# 90_IR_Receiver_LED.net
KiCad netlist of a schematic drawn in Altium Designer
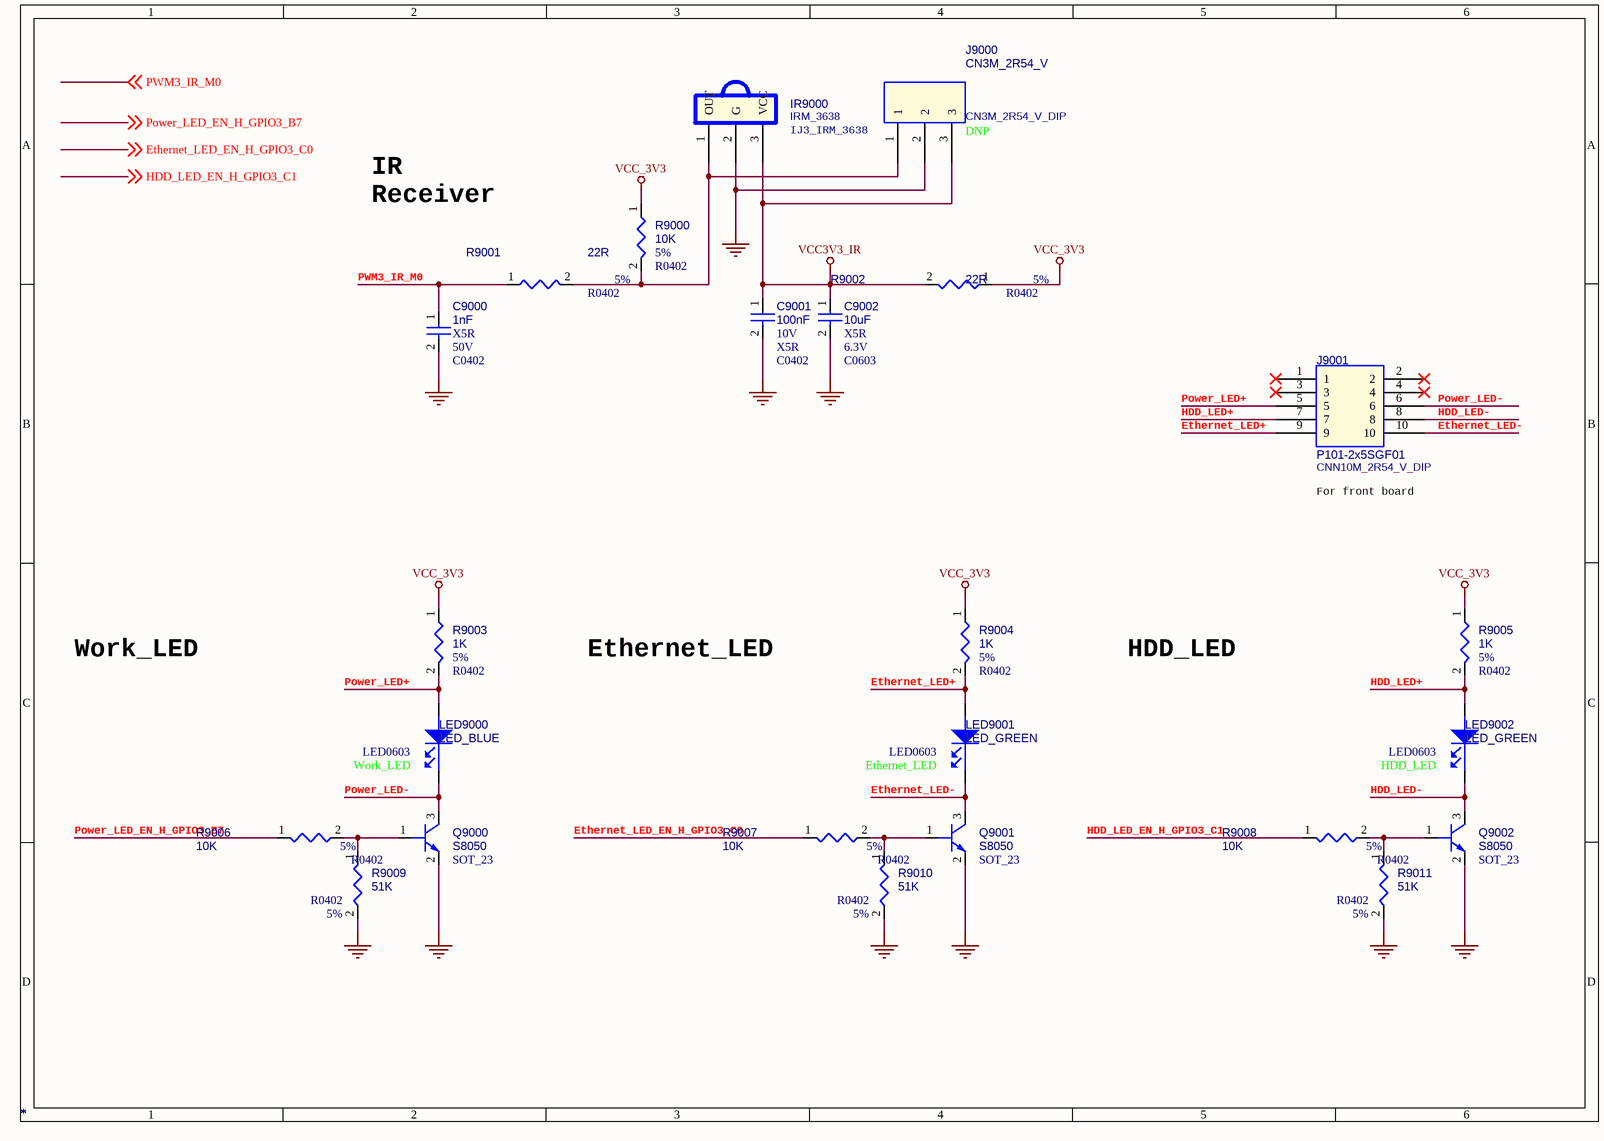
[diagram p0: 90.IR Receiver_LED.SchDoc]

(export (version "E")
  (design (tool "Eeschema 10.0.6"))
  (components
    (comp (ref "C9000")
      (value "*")
      (footprint "C0402")
      (description "cap,1.00nF,+/-10%,50V,X5R,C0402")
      (fields
        (field (name "VOLTAGE") "50V")
        (field (name "PCB FOOTPRINT") "C0402")
        (field (name "DIELECTRIC") "X5R")
        (field (name "MANUFACTURER") "TDK")
        (field (name "TOLERANCE") "10%")
        (field (name "ALTIUM_UNNAMED_1") "1nF")
        (field (name "CREATED BY") "JJJ")
      )
      (libsource (lib "*") (part "CAP NP"))
    )
    (comp (ref "C9001")
      (value "*")
      (footprint "C0402")
      (description "cap,100.00nF,+/-10%,10V,X5R,C0402")
      (fields
        (field (name "VOLTAGE") "10V")
        (field (name "PCB FOOTPRINT") "C0402")
        (field (name "DIELECTRIC") "X5R")
        (field (name "MANUFACTURER") "TDK")
        (field (name "TOLERANCE") "10%")
        (field (name "ALTIUM_UNNAMED_1") "100nF")
        (field (name "CREATED BY") "JJJ")
      )
      (libsource (lib "*") (part "CAP NP"))
    )
    (comp (ref "C9002")
      (value "*")
      (footprint "C0603")
      (description "cap,10.00uF,+/-10%,6.3V,X5R,C0603")
      (fields
        (field (name "VOLTAGE") "6.3V")
        (field (name "PCB FOOTPRINT") "C0603")
        (field (name "DIELECTRIC") "X5R")
        (field (name "MANUFACTURER") "TDK")
        (field (name "TOLERANCE") "10%")
        (field (name "ALTIUM_UNNAMED_1") "10uF")
        (field (name "CREATED BY") "JJJ")
      )
      (libsource (lib "*") (part "CAP NP"))
    )
    (comp (ref "IR9000")
      (value "*")
      (footprint "IR3DIP")
      (description "ємНвЅУКХН·")
      (fields
        (field (name "PCB FOOTPRINT") "IJ3_IRM_3638")
        (field (name "MANUFACTURER") "ТЪ№в")
        (field (name "MANUFACTURER PART NUMBER") "IRM_3638")
        (field (name "ALTIUM_UNNAMED_1") "IRM_3638")
        (field (name "CREATED BY") "JJJ")
      )
      (libsource (lib "*") (part "IRM_0"))
    )
    (comp (ref "J9000")
      (value "*")
      (footprint "DIP3_1X3_2R54")
      (description "µҐЕЕ3PINЈЁјдѕа2.54mmЈ©І»ґш·А»¤ЗЅµДІеХл")
      (fields
        (field (name "PCB FOOTPRINT") "CN3M_2R54_V_DIP")
        (field (name "OPTION") "DNP")
        (field (name "MANUFACTURER") "НъїЖґп")
        (field (name "MANUFACTURER PART NUMBER") "CON3M_1X3_2R54_V")
        (field (name "ALTIUM_UNNAMED_1") "CN3M_2R54_V")
        (field (name "CREATED BY") "JJJ")
      )
      (libsource (lib "*") (part "CON3_1X3"))
    )
    (comp (ref "J9001")
      (value "*")
      (footprint "JTAG_2X10_2R54")
      (description "Л«ЕЕ10PINЈЁјдѕа2.54mmЈ©І»ґш·А»¤ЗЅµДІеХл,БўКЅЈ¬№«Чщ")
      (fields
        (field (name "PCB FOOTPRINT") "CNN10M_2R54_V_DIP")
        (field (name "MANUFACTURER") "СwХэµзЧУ")
        (field (name "MANUFACTURER PART NUMBER") "P101-2x10SGF01")
        (field (name "ALTIUM_UNNAMED_1") "P101-2x5SGF01")
        (field (name "CREATED BY") "JJJ")
      )
      (libsource (lib "*") (part "CON20_0"))
    )
    (comp (ref "LED9000")
      (value "*")
      (footprint "LED0603")
      (description "МщЖ¬LEDµЖЈ¬0603Ј¬А¶Й«")
      (fields
        (field (name "PCB FOOTPRINT") "LED0603")
        (field (name "OPTION") "Work_LED")
        (field (name "ALTIUM_UNNAMED_1") "LED_BLUE")
        (field (name "CREATED BY") "JJJ")
      )
      (libsource (lib "*") (part "LED"))
    )
    (comp (ref "LED9001")
      (value "*")
      (footprint "LED0603")
      (description "МщЖ¬LEDµЖЈ¬0603Ј¬ВМЙ«")
      (fields
        (field (name "PCB FOOTPRINT") "LED0603")
        (field (name "OPTION") "Ethernet_LED")
        (field (name "ALTIUM_UNNAMED_1") "LED_GREEN")
        (field (name "CREATED BY") "JJJ")
      )
      (libsource (lib "*") (part "LED"))
    )
    (comp (ref "LED9002")
      (value "*")
      (footprint "LED0603")
      (description "МщЖ¬LEDµЖЈ¬0603Ј¬ВМЙ«")
      (fields
        (field (name "PCB FOOTPRINT") "LED0603")
        (field (name "OPTION") "HDD_LED")
        (field (name "ALTIUM_UNNAMED_1") "LED_GREEN")
        (field (name "CREATED BY") "JJJ")
      )
      (libsource (lib "*") (part "LED"))
    )
    (comp (ref "Q9000")
      (value "*")
      (footprint "SOT_23")
      (description "S8050,SOT23")
      (fields
        (field (name "PCB FOOTPRINT") "SOT_23")
        (field (name "MANUFACTURER") "і¤µз")
        (field (name "ALTIUM_UNNAMED_1") "S8050")
        (field (name "CREATED BY") "JJJ")
      )
      (libsource (lib "*") (part "NPN"))
    )
    (comp (ref "Q9001")
      (value "*")
      (footprint "SOT_23")
      (description "S8050,SOT23")
      (fields
        (field (name "PCB FOOTPRINT") "SOT_23")
        (field (name "MANUFACTURER") "і¤µз")
        (field (name "ALTIUM_UNNAMED_1") "S8050")
        (field (name "CREATED BY") "JJJ")
      )
      (libsource (lib "*") (part "NPN"))
    )
    (comp (ref "Q9002")
      (value "*")
      (footprint "SOT_23")
      (description "S8050,SOT23")
      (fields
        (field (name "PCB FOOTPRINT") "SOT_23")
        (field (name "MANUFACTURER") "і¤µз")
        (field (name "ALTIUM_UNNAMED_1") "S8050")
        (field (name "CREATED BY") "JJJ")
      )
      (libsource (lib "*") (part "NPN"))
    )
    (comp (ref "R9000")
      (value "*")
      (footprint "R0402")
      (description "НЁУГєсД¤µзЧи,10K,+/-5%,R0402,1/16W.")
      (fields
        (field (name "PCB FOOTPRINT") "R0402")
        (field (name "TOLERANCE") "5%")
        (field (name "MANUFACTURER") "YAGEO")
        (field (name "ALTIUM_UNNAMED_1") "10K")
        (field (name "CREATED BY") "YTL")
      )
      (libsource (lib "*") (part "RESISTOR_Dup1"))
    )
    (comp (ref "R9001")
      (value "*")
      (footprint "R0402")
      (description "НЁУГєсД¤µзЧи,22R,+/-5%,R0402,1/16W.")
      (fields
        (field (name "PCB FOOTPRINT") "R0402")
        (field (name "TOLERANCE") "5%")
        (field (name "MANUFACTURER") "YAGEO")
        (field (name "ALTIUM_UNNAMED_1") "22R")
        (field (name "CREATED BY") "YTL")
      )
      (libsource (lib "*") (part "RESISTOR_Dup1"))
    )
    (comp (ref "R9002")
      (value "*")
      (footprint "R0402")
      (description "НЁУГєсД¤µзЧи,22R,+/-5%,R0402,1/16W.")
      (fields
        (field (name "PCB FOOTPRINT") "R0402")
        (field (name "TOLERANCE") "5%")
        (field (name "MANUFACTURER") "YAGEO")
        (field (name "ALTIUM_UNNAMED_1") "22R")
        (field (name "CREATED BY") "YTL")
      )
      (libsource (lib "*") (part "RESISTOR_Dup1"))
    )
    (comp (ref "R9003")
      (value "*")
      (footprint "R0402")
      (description "НЁУГєсД¤µзЧи,1K,+/-5%,R0402,1/16W.")
      (fields
        (field (name "PCB FOOTPRINT") "R0402")
        (field (name "TOLERANCE") "5%")
        (field (name "MANUFACTURER") "YAGEO")
        (field (name "ALTIUM_UNNAMED_1") "1K")
        (field (name "CREATED BY") "YTL")
      )
      (libsource (lib "*") (part "RESISTOR_Dup1"))
    )
    (comp (ref "R9004")
      (value "*")
      (footprint "R0402")
      (description "НЁУГєсД¤µзЧи,1K,+/-5%,R0402,1/16W.")
      (fields
        (field (name "PCB FOOTPRINT") "R0402")
        (field (name "TOLERANCE") "5%")
        (field (name "MANUFACTURER") "YAGEO")
        (field (name "ALTIUM_UNNAMED_1") "1K")
        (field (name "CREATED BY") "YTL")
      )
      (libsource (lib "*") (part "RESISTOR_Dup1"))
    )
    (comp (ref "R9005")
      (value "*")
      (footprint "R0402")
      (description "НЁУГєсД¤µзЧи,1K,+/-5%,R0402,1/16W.")
      (fields
        (field (name "PCB FOOTPRINT") "R0402")
        (field (name "TOLERANCE") "5%")
        (field (name "MANUFACTURER") "YAGEO")
        (field (name "ALTIUM_UNNAMED_1") "1K")
        (field (name "CREATED BY") "YTL")
      )
      (libsource (lib "*") (part "RESISTOR_Dup1"))
    )
    (comp (ref "R9006")
      (value "*")
      (footprint "R0402")
      (description "НЁУГєсД¤µзЧи,10K,+/-5%,R0402,1/16W.")
      (fields
        (field (name "PCB FOOTPRINT") "R0402")
        (field (name "TOLERANCE") "5%")
        (field (name "MANUFACTURER") "YAGEO")
        (field (name "ALTIUM_UNNAMED_1") "10K")
        (field (name "CREATED BY") "YTL")
      )
      (libsource (lib "*") (part "RESISTOR_Dup1"))
    )
    (comp (ref "R9007")
      (value "*")
      (footprint "R0402")
      (description "НЁУГєсД¤µзЧи,10K,+/-5%,R0402,1/16W.")
      (fields
        (field (name "PCB FOOTPRINT") "R0402")
        (field (name "TOLERANCE") "5%")
        (field (name "MANUFACTURER") "YAGEO")
        (field (name "ALTIUM_UNNAMED_1") "10K")
        (field (name "CREATED BY") "YTL")
      )
      (libsource (lib "*") (part "RESISTOR_Dup1"))
    )
    (comp (ref "R9008")
      (value "*")
      (footprint "R0402")
      (description "НЁУГєсД¤µзЧи,10K,+/-5%,R0402,1/16W.")
      (fields
        (field (name "PCB FOOTPRINT") "R0402")
        (field (name "TOLERANCE") "5%")
        (field (name "MANUFACTURER") "YAGEO")
        (field (name "ALTIUM_UNNAMED_1") "10K")
        (field (name "CREATED BY") "YTL")
      )
      (libsource (lib "*") (part "RESISTOR_Dup1"))
    )
    (comp (ref "R9009")
      (value "*")
      (footprint "R0402")
      (description "НЁУГєсД¤µзЧи,51K,+/-5%,R0402,1/16W.")
      (fields
        (field (name "PCB FOOTPRINT") "R0402")
        (field (name "TOLERANCE") "5%")
        (field (name "MANUFACTURER") "YAGEO")
        (field (name "ALTIUM_UNNAMED_1") "51K")
        (field (name "CREATED BY") "YTL")
      )
      (libsource (lib "*") (part "RESISTOR_Dup1"))
    )
    (comp (ref "R9010")
      (value "*")
      (footprint "R0402")
      (description "НЁУГєсД¤µзЧи,51K,+/-5%,R0402,1/16W.")
      (fields
        (field (name "PCB FOOTPRINT") "R0402")
        (field (name "TOLERANCE") "5%")
        (field (name "MANUFACTURER") "YAGEO")
        (field (name "ALTIUM_UNNAMED_1") "51K")
        (field (name "CREATED BY") "YTL")
      )
      (libsource (lib "*") (part "RESISTOR_Dup1"))
    )
    (comp (ref "R9011")
      (value "*")
      (footprint "R0402")
      (description "НЁУГєсД¤µзЧи,51K,+/-5%,R0402,1/16W.")
      (fields
        (field (name "PCB FOOTPRINT") "R0402")
        (field (name "TOLERANCE") "5%")
        (field (name "MANUFACTURER") "YAGEO")
        (field (name "ALTIUM_UNNAMED_1") "51K")
        (field (name "CREATED BY") "YTL")
      )
      (libsource (lib "*") (part "RESISTOR_Dup1"))
    )
  )
  (nets
    (net (code "1") (name "/Ethernet_LED+") (class "Default")
      (node (ref "J9001") (pin "9") (pinfunction "9_9") (pintype "passive"))
      (node (ref "LED9001") (pin "1") (pinfunction "ANODE_1") (pintype "passive"))
      (node (ref "R9004") (pin "2") (pinfunction "2_2") (pintype "passive"))
    )
    (net (code "2") (name "/Ethernet_LED-") (class "Default")
      (node (ref "J9001") (pin "10") (pinfunction "10_10") (pintype "passive"))
      (node (ref "LED9001") (pin "2") (pinfunction "CATHODE_2") (pintype "passive"))
      (node (ref "Q9001") (pin "3") (pinfunction "COLLECTOR_3") (pintype "passive"))
    )
    (net (code "3") (name "/HDD_LED+") (class "Default")
      (node (ref "J9001") (pin "7") (pinfunction "7_7") (pintype "passive"))
      (node (ref "LED9002") (pin "1") (pinfunction "ANODE_1") (pintype "passive"))
      (node (ref "R9005") (pin "2") (pinfunction "2_2") (pintype "passive"))
    )
    (net (code "4") (name "/HDD_LED-") (class "Default")
      (node (ref "J9001") (pin "8") (pinfunction "8_8") (pintype "passive"))
      (node (ref "LED9002") (pin "2") (pinfunction "CATHODE_2") (pintype "passive"))
      (node (ref "Q9002") (pin "3") (pinfunction "COLLECTOR_3") (pintype "passive"))
    )
    (net (code "5") (name "/Power_LED+") (class "Default")
      (node (ref "J9001") (pin "5") (pinfunction "5_5") (pintype "passive"))
      (node (ref "LED9000") (pin "1") (pinfunction "ANODE_1") (pintype "passive"))
      (node (ref "R9003") (pin "2") (pinfunction "2_2") (pintype "passive"))
    )
    (net (code "6") (name "/Power_LED-") (class "Default")
      (node (ref "J9001") (pin "6") (pinfunction "6_6") (pintype "passive"))
      (node (ref "LED9000") (pin "2") (pinfunction "CATHODE_2") (pintype "passive"))
      (node (ref "Q9000") (pin "3") (pinfunction "COLLECTOR_3") (pintype "passive"))
    )
    (net (code "7") (name "Ethernet_LED_EN_H_GPIO3_C0") (class "Default")
      (node (ref "R9007") (pin "1") (pinfunction "1_1") (pintype "passive"))
    )
    (net (code "8") (name "GND") (class "Default")
      (node (ref "C9000") (pin "2") (pinfunction "2_2") (pintype "passive"))
      (node (ref "C9001") (pin "2") (pinfunction "2_2") (pintype "passive"))
      (node (ref "C9002") (pin "2") (pinfunction "2_2") (pintype "passive"))
      (node (ref "IR9000") (pin "2") (pinfunction "G_2") (pintype "passive"))
      (node (ref "J9000") (pin "2") (pinfunction "2_2") (pintype "passive"))
      (node (ref "Q9000") (pin "2") (pinfunction "EMITTER_2") (pintype "passive"))
      (node (ref "Q9001") (pin "2") (pinfunction "EMITTER_2") (pintype "passive"))
      (node (ref "Q9002") (pin "2") (pinfunction "EMITTER_2") (pintype "passive"))
      (node (ref "R9009") (pin "2") (pinfunction "2_2") (pintype "passive"))
      (node (ref "R9010") (pin "2") (pinfunction "2_2") (pintype "passive"))
      (node (ref "R9011") (pin "2") (pinfunction "2_2") (pintype "passive"))
    )
    (net (code "9") (name "HDD_LED_EN_H_GPIO3_C1") (class "Default")
      (node (ref "R9008") (pin "1") (pinfunction "1_1") (pintype "passive"))
    )
    (net (code "10") (name "Net-(IR9000-OUT)") (class "Default")
      (node (ref "IR9000") (pin "1") (pinfunction "OUT_1") (pintype "passive"))
      (node (ref "J9000") (pin "1") (pinfunction "1_1") (pintype "passive"))
      (node (ref "R9000") (pin "2") (pinfunction "2_2") (pintype "passive"))
      (node (ref "R9001") (pin "2") (pinfunction "2_2") (pintype "passive"))
    )
    (net (code "11") (name "Net-(Q9000-BASE)") (class "Default")
      (node (ref "Q9000") (pin "1") (pinfunction "BASE_1") (pintype "passive"))
      (node (ref "R9006") (pin "2") (pinfunction "2_2") (pintype "passive"))
      (node (ref "R9009") (pin "1") (pinfunction "1_1") (pintype "passive"))
    )
    (net (code "12") (name "Net-(Q9001-BASE)") (class "Default")
      (node (ref "Q9001") (pin "1") (pinfunction "BASE_1") (pintype "passive"))
      (node (ref "R9007") (pin "2") (pinfunction "2_2") (pintype "passive"))
      (node (ref "R9010") (pin "1") (pinfunction "1_1") (pintype "passive"))
    )
    (net (code "13") (name "Net-(Q9002-BASE)") (class "Default")
      (node (ref "Q9002") (pin "1") (pinfunction "BASE_1") (pintype "passive"))
      (node (ref "R9008") (pin "2") (pinfunction "2_2") (pintype "passive"))
      (node (ref "R9011") (pin "1") (pinfunction "1_1") (pintype "passive"))
    )
    (net (code "14") (name "PWM3_IR_M0") (class "Default")
      (node (ref "C9000") (pin "1") (pinfunction "1_1") (pintype "passive"))
      (node (ref "R9001") (pin "1") (pinfunction "1_1") (pintype "passive"))
    )
    (net (code "15") (name "Power_LED_EN_H_GPIO3_B7") (class "Default")
      (node (ref "R9006") (pin "1") (pinfunction "1_1") (pintype "passive"))
    )
    (net (code "16") (name "VCC3V3_IR") (class "Default")
      (node (ref "C9001") (pin "1") (pinfunction "1_1") (pintype "passive"))
      (node (ref "C9002") (pin "1") (pinfunction "1_1") (pintype "passive"))
      (node (ref "IR9000") (pin "3") (pinfunction "VCC_3") (pintype "passive"))
      (node (ref "J9000") (pin "3") (pinfunction "3_3") (pintype "passive"))
      (node (ref "R9002") (pin "2") (pinfunction "2_2") (pintype "passive"))
    )
    (net (code "17") (name "VCC_3V3") (class "Default")
      (node (ref "R9000") (pin "1") (pinfunction "1_1") (pintype "passive"))
      (node (ref "R9002") (pin "1") (pinfunction "1_1") (pintype "passive"))
      (node (ref "R9003") (pin "1") (pinfunction "1_1") (pintype "passive"))
      (node (ref "R9004") (pin "1") (pinfunction "1_1") (pintype "passive"))
      (node (ref "R9005") (pin "1") (pinfunction "1_1") (pintype "passive"))
    )
    (net (code "18") (name "unconnected-(J9001-Pad1)") (class "Default")
      (node (ref "J9001") (pin "1") (pinfunction "1_1") (pintype "passive+no_connect"))
    )
    (net (code "19") (name "unconnected-(J9001-Pad2)") (class "Default")
      (node (ref "J9001") (pin "2") (pinfunction "2_2") (pintype "passive+no_connect"))
    )
    (net (code "20") (name "unconnected-(J9001-Pad3)") (class "Default")
      (node (ref "J9001") (pin "3") (pinfunction "3_3") (pintype "passive+no_connect"))
    )
    (net (code "21") (name "unconnected-(J9001-Pad4)") (class "Default")
      (node (ref "J9001") (pin "4") (pinfunction "4_4") (pintype "passive+no_connect"))
    )
  )
)
